# bmsMaster_isospi.net
KiCad netlist of a schematic drawn in Altium Designer
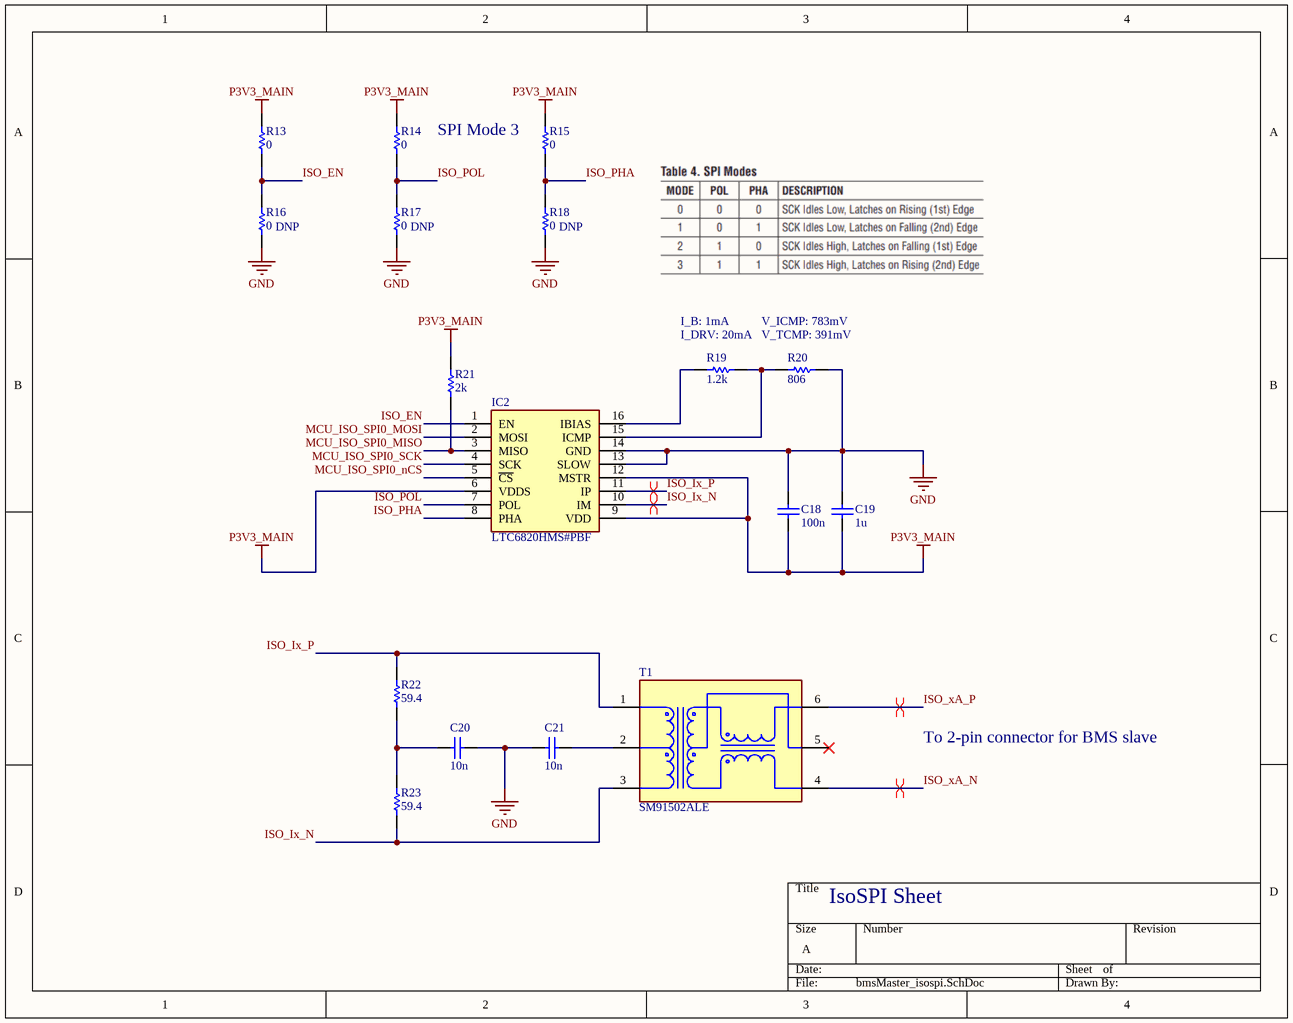
[diagram p0: bmsMaster_isospi.SchDoc]

(export (version "E")
  (design (tool "Eeschema 10.0.6"))
  (components
    (comp (ref "C18")
      (value "100n")
      (description "Capacitor")
      (libsource (lib "Simulation Generic Components") (part "Capacitor"))
    )
    (comp (ref "C19")
      (value "1u")
      (description "Capacitor")
      (libsource (lib "Simulation Generic Components") (part "Capacitor"))
    )
    (comp (ref "C20")
      (value "10n")
      (description "Capacitor")
      (libsource (lib "Simulation Generic Components") (part "Capacitor"))
    )
    (comp (ref "C21")
      (value "10n")
      (description "Capacitor")
      (libsource (lib "Simulation Generic Components") (part "Capacitor"))
    )
    (comp (ref "IC2")
      (value "LTC6820HMS#PBF")
      (footprint "SamacSys:SOP50P490X110-16N")
      (description "Integrated Circuit")
      (fields (field (name "MOUSER PART NUMBER") "584-LTC6820HMS#PBF"))
      (libsource (lib "*") (part "LTC6820HMS#PBF"))
    )
    (comp (ref "R13")
      (value "0")
      (description "Resistor")
      (libsource (lib "Simulation Generic Components") (part "Resistor"))
    )
    (comp (ref "R14")
      (value "0")
      (description "Resistor")
      (libsource (lib "Simulation Generic Components") (part "Resistor"))
    )
    (comp (ref "R15")
      (value "0")
      (description "Resistor")
      (libsource (lib "Simulation Generic Components") (part "Resistor"))
    )
    (comp (ref "R16")
      (value "0")
      (description "Resistor")
      (libsource (lib "Simulation Generic Components") (part "Resistor"))
    )
    (comp (ref "R17")
      (value "0")
      (description "Resistor")
      (libsource (lib "Simulation Generic Components") (part "Resistor"))
    )
    (comp (ref "R18")
      (value "0")
      (description "Resistor")
      (libsource (lib "Simulation Generic Components") (part "Resistor"))
    )
    (comp (ref "R19")
      (value "1.2k")
      (description "Resistor")
      (libsource (lib "Simulation Generic Components") (part "Resistor"))
    )
    (comp (ref "R20")
      (value "806")
      (description "Resistor")
      (libsource (lib "Simulation Generic Components") (part "Resistor"))
    )
    (comp (ref "R21")
      (value "2k")
      (description "Resistor")
      (libsource (lib "Simulation Generic Components") (part "Resistor"))
    )
    (comp (ref "R22")
      (value "59.4")
      (description "Resistor")
      (libsource (lib "Simulation Generic Components") (part "Resistor"))
    )
    (comp (ref "R23")
      (value "59.4")
      (description "Resistor")
      (libsource (lib "Simulation Generic Components") (part "Resistor"))
    )
    (comp (ref "T1")
      (value "SM91502ALE")
      (footprint "FP-SM91502ALE-MFG")
      (description "BMS XFORMER 1-CH 1000V AECQ +125")
      (fields
        (field (name "MANUFACTURER") "Bourns")
        (field (name "OCTOPART") "https://octopart.com/sm91502ale-bourns-95732123")
      )
      (libsource (lib "Altium Content Vault") (part "554ff5199021d68917f526d8699f58a"))
    )
  )
  (nets
    (net (code "1") (name "/ISO_EN") (class "Default")
      (node (ref "IC2") (pin "1") (pinfunction "EN_1") (pintype "passive"))
      (node (ref "R13") (pin "1") (pinfunction "1_1") (pintype "passive"))
      (node (ref "R16") (pin "2") (pinfunction "2_2") (pintype "passive"))
    )
    (net (code "2") (name "/ISO_Ix_N") (class "Default")
      (node (ref "IC2") (pin "10") (pinfunction "IM_10") (pintype "passive"))
      (node (ref "R23") (pin "1") (pinfunction "1_1") (pintype "passive"))
      (node (ref "T1") (pin "3") (pinfunction "3_3") (pintype "passive"))
    )
    (net (code "3") (name "/ISO_Ix_P") (class "Default")
      (node (ref "IC2") (pin "11") (pinfunction "IP_11") (pintype "passive"))
      (node (ref "R22") (pin "2") (pinfunction "2_2") (pintype "passive"))
      (node (ref "T1") (pin "1") (pinfunction "1_1") (pintype "passive"))
    )
    (net (code "4") (name "/ISO_PHA") (class "Default")
      (node (ref "IC2") (pin "8") (pinfunction "PHA_8") (pintype "passive"))
      (node (ref "R15") (pin "1") (pinfunction "1_1") (pintype "passive"))
      (node (ref "R18") (pin "2") (pinfunction "2_2") (pintype "passive"))
    )
    (net (code "5") (name "/ISO_POL") (class "Default")
      (node (ref "IC2") (pin "7") (pinfunction "POL_7") (pintype "passive"))
      (node (ref "R14") (pin "1") (pinfunction "1_1") (pintype "passive"))
      (node (ref "R17") (pin "2") (pinfunction "2_2") (pintype "passive"))
    )
    (net (code "6") (name "/ISO_xA_N") (class "Default")
      (node (ref "T1") (pin "4") (pinfunction "4_4") (pintype "passive"))
    )
    (net (code "7") (name "/ISO_xA_P") (class "Default")
      (node (ref "T1") (pin "6") (pinfunction "6_6") (pintype "passive"))
    )
    (net (code "8") (name "/MCU_ISO_SPI0_MISO") (class "Default")
      (node (ref "IC2") (pin "3") (pinfunction "MISO_3") (pintype "passive"))
      (node (ref "R21") (pin "1") (pinfunction "1_1") (pintype "passive"))
    )
    (net (code "9") (name "/MCU_ISO_SPI0_MOSI") (class "Default")
      (node (ref "IC2") (pin "2") (pinfunction "MOSI_2") (pintype "passive"))
    )
    (net (code "10") (name "/MCU_ISO_SPI0_SCK") (class "Default")
      (node (ref "IC2") (pin "4") (pinfunction "SCK_4") (pintype "passive"))
    )
    (net (code "11") (name "/MCU_ISO_SPI0_nCS") (class "Default")
      (node (ref "IC2") (pin "5") (pinfunction "~{CS}_5") (pintype "passive"))
    )
    (net (code "12") (name "GND") (class "Default")
      (node (ref "C18") (pin "2") (pinfunction "2_2") (pintype "passive"))
      (node (ref "C19") (pin "2") (pinfunction "2_2") (pintype "passive"))
      (node (ref "C20") (pin "1") (pinfunction "1_1") (pintype "passive"))
      (node (ref "C21") (pin "1") (pinfunction "1_1") (pintype "passive"))
      (node (ref "IC2") (pin "13") (pinfunction "SLOW_13") (pintype "passive"))
      (node (ref "IC2") (pin "14") (pinfunction "GND_14") (pintype "passive"))
      (node (ref "R16") (pin "1") (pinfunction "1_1") (pintype "passive"))
      (node (ref "R17") (pin "1") (pinfunction "1_1") (pintype "passive"))
      (node (ref "R18") (pin "1") (pinfunction "1_1") (pintype "passive"))
      (node (ref "R20") (pin "2") (pinfunction "2_2") (pintype "passive"))
    )
    (net (code "13") (name "Net-(C20-Pad2)") (class "Default")
      (node (ref "C20") (pin "2") (pinfunction "2_2") (pintype "passive"))
      (node (ref "R22") (pin "1") (pinfunction "1_1") (pintype "passive"))
      (node (ref "R23") (pin "2") (pinfunction "2_2") (pintype "passive"))
    )
    (net (code "14") (name "Net-(C21-Pad2)") (class "Default")
      (node (ref "C21") (pin "2") (pinfunction "2_2") (pintype "passive"))
      (node (ref "T1") (pin "2") (pinfunction "2_2") (pintype "passive"))
    )
    (net (code "15") (name "Net-(IC2-IBIAS)") (class "Default")
      (node (ref "IC2") (pin "16") (pinfunction "IBIAS_16") (pintype "passive"))
      (node (ref "R19") (pin "1") (pinfunction "1_1") (pintype "passive"))
    )
    (net (code "16") (name "Net-(IC2-ICMP)") (class "Default")
      (node (ref "IC2") (pin "15") (pinfunction "ICMP_15") (pintype "passive"))
      (node (ref "R19") (pin "2") (pinfunction "2_2") (pintype "passive"))
      (node (ref "R20") (pin "1") (pinfunction "1_1") (pintype "passive"))
    )
    (net (code "17") (name "P3V3_MAIN") (class "Default")
      (node (ref "C18") (pin "1") (pinfunction "1_1") (pintype "passive"))
      (node (ref "C19") (pin "1") (pinfunction "1_1") (pintype "passive"))
      (node (ref "IC2") (pin "12") (pinfunction "MSTR_12") (pintype "passive"))
      (node (ref "IC2") (pin "6") (pinfunction "VDDS_6") (pintype "passive"))
      (node (ref "IC2") (pin "9") (pinfunction "VDD_9") (pintype "passive"))
      (node (ref "R13") (pin "2") (pinfunction "2_2") (pintype "passive"))
      (node (ref "R14") (pin "2") (pinfunction "2_2") (pintype "passive"))
      (node (ref "R15") (pin "2") (pinfunction "2_2") (pintype "passive"))
      (node (ref "R21") (pin "2") (pinfunction "2_2") (pintype "passive"))
    )
    (net (code "18") (name "unconnected-(T1-Pad5)") (class "Default")
      (node (ref "T1") (pin "5") (pinfunction "5_5") (pintype "passive+no_connect"))
    )
  )
)
